# IR_ARRAY_IMG.net
KiCad netlist of a schematic drawn in EAGLE
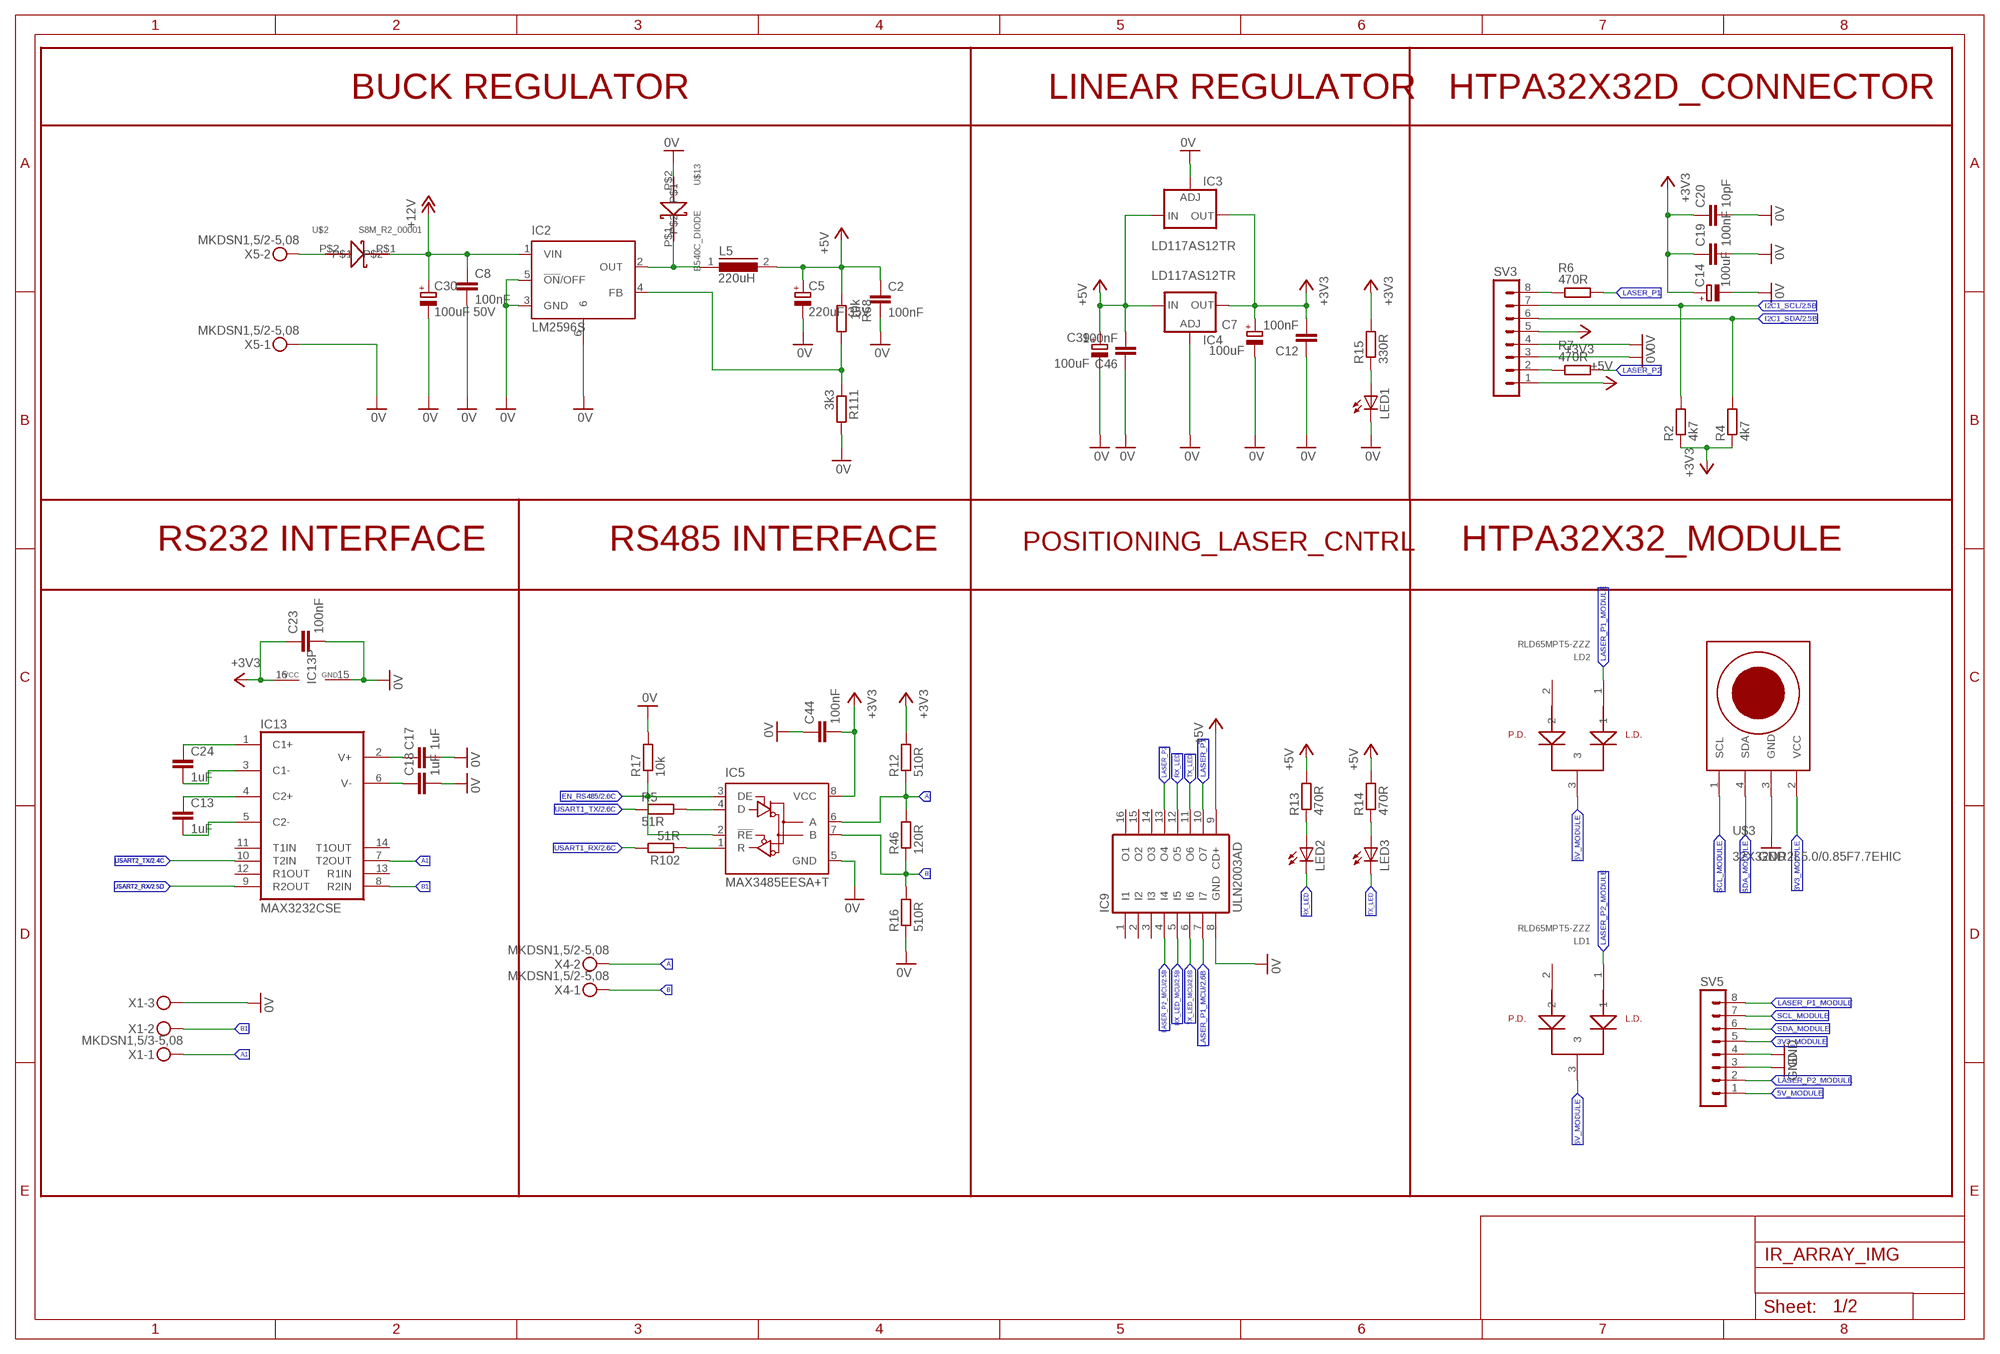
[diagram p0: schematic, sheet 1]
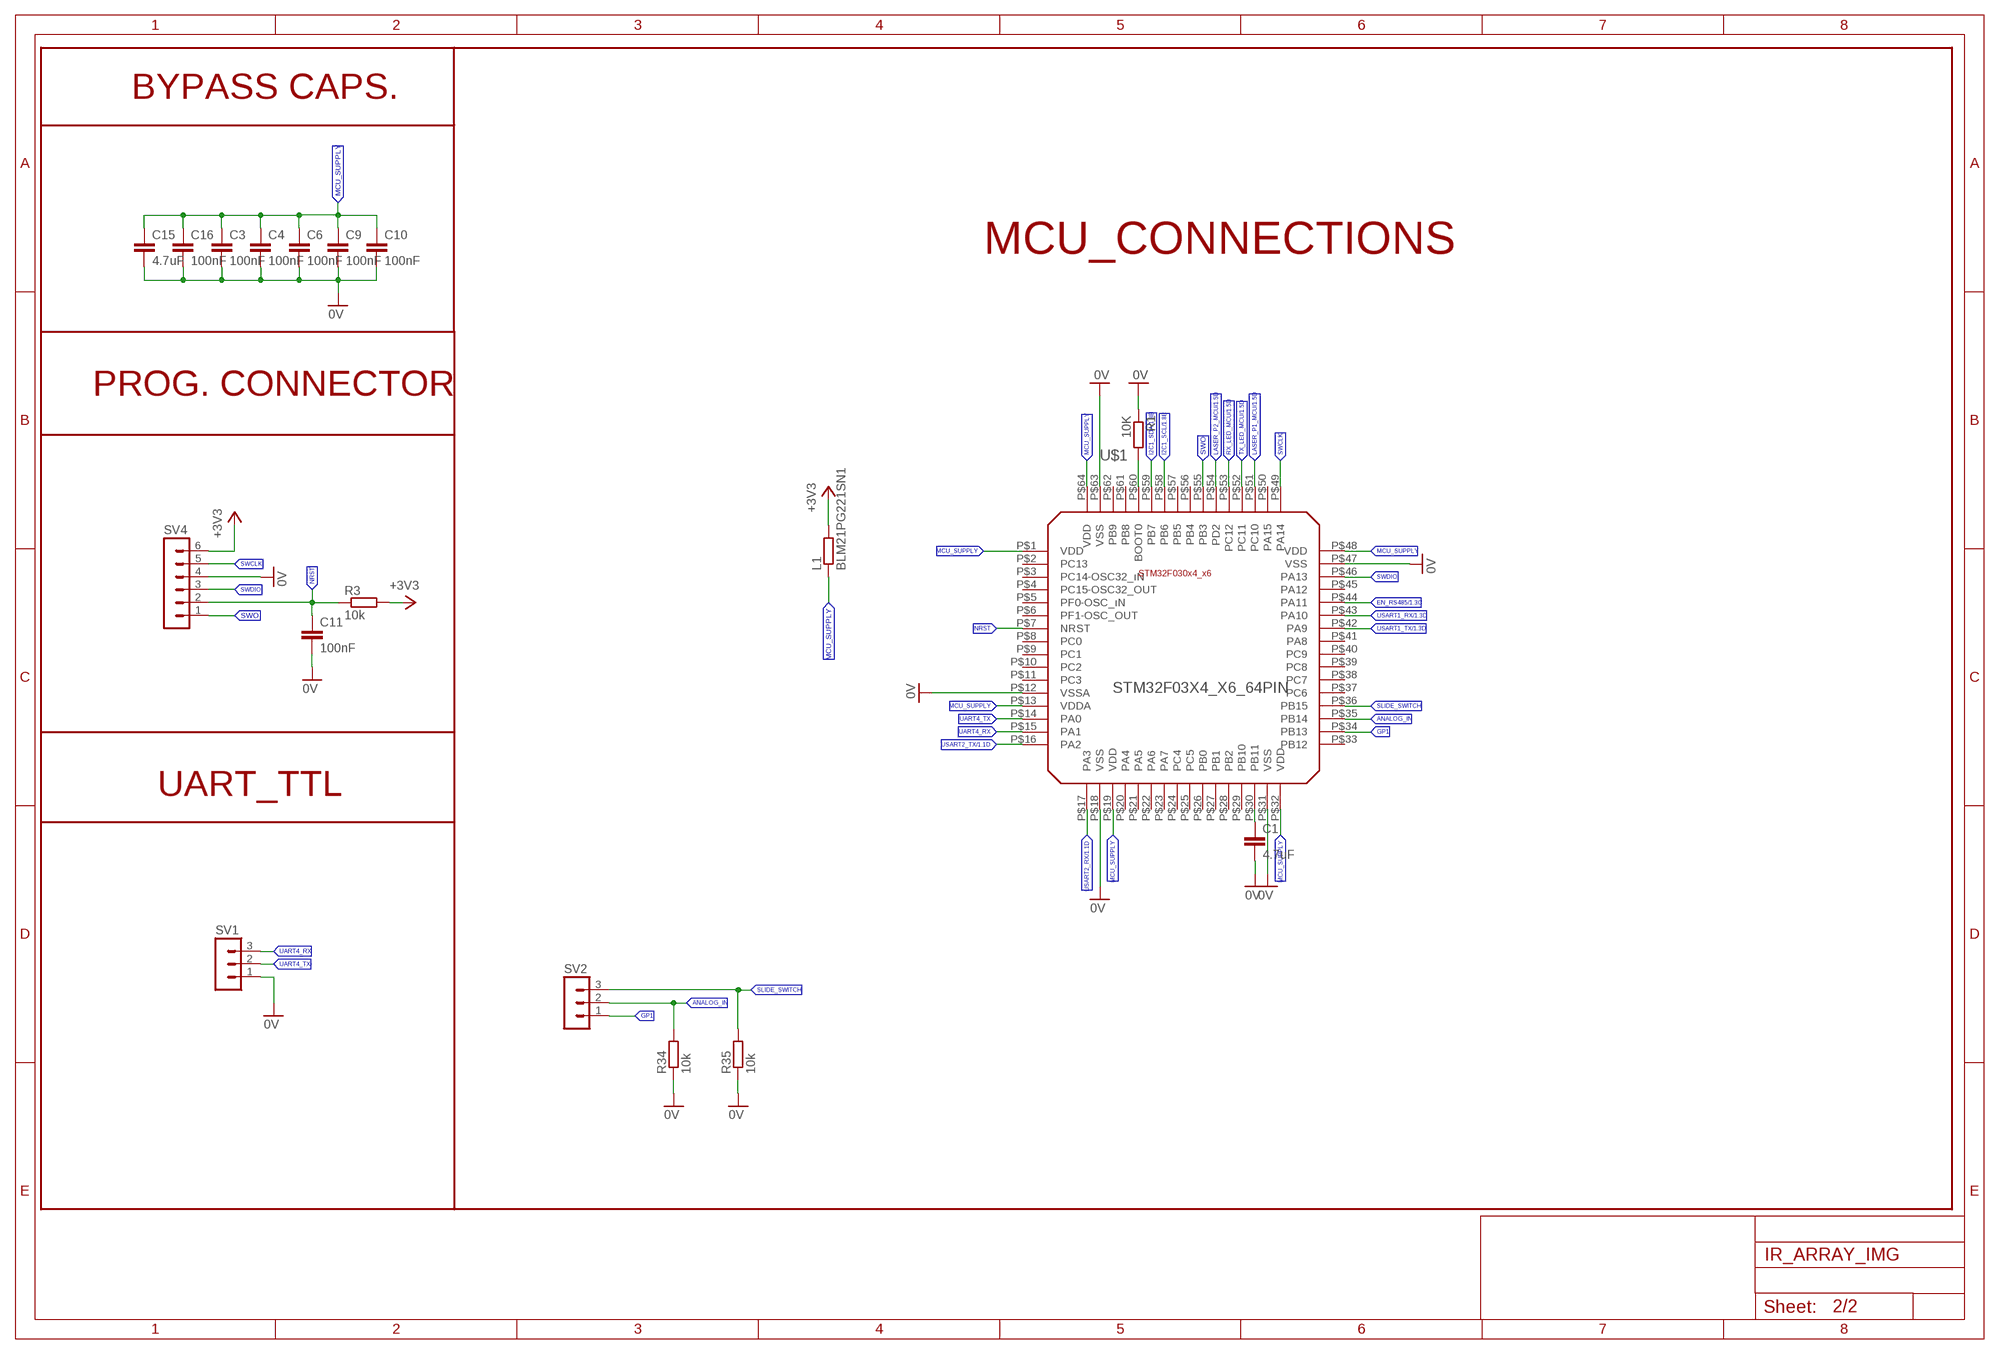
[diagram p1: schematic, sheet 2]

(export (version "E")
  (design (tool "Eeschema 10.0.6"))
  (components
    (comp (ref "C2")
      (value "100nF")
      (footprint "eagle-import:C0805")
      (libsource (lib "eagle-import") (part "C-EUC0805"))
    )
    (comp (ref "C5")
      (value "220uF 35V")
      (footprint "eagle-import:153CLV-0810")
      (libsource (lib "eagle-import") (part "CPOL-EU153CLV-0810"))
    )
    (comp (ref "C7")
      (value "100uF")
      (footprint "eagle-import:153CLV-0605")
      (libsource (lib "eagle-import") (part "CPOL-EU153CLV-0605"))
    )
    (comp (ref "C8")
      (value "100nF")
      (footprint "eagle-import:C0805")
      (libsource (lib "eagle-import") (part "C-EUC0805"))
    )
    (comp (ref "C12")
      (value "100nF")
      (footprint "eagle-import:C0603")
      (libsource (lib "eagle-import") (part "C-EUC0603"))
    )
    (comp (ref "C13")
      (value "1uF")
      (footprint "eagle-import:C1206")
      (libsource (lib "eagle-import") (part "C-EUC1206"))
    )
    (comp (ref "C14")
      (value "100uF")
      (footprint "eagle-import:C_6032-28R")
      (libsource (lib "eagle-import") (part "CPOL-EUC/6032-28R"))
    )
    (comp (ref "C17")
      (value "1uF")
      (footprint "eagle-import:C1206")
      (libsource (lib "eagle-import") (part "C-EUC1206"))
    )
    (comp (ref "C18")
      (value "1uF")
      (footprint "eagle-import:C1206")
      (libsource (lib "eagle-import") (part "C-EUC1206"))
    )
    (comp (ref "C19")
      (value "100nF")
      (footprint "eagle-import:C0603")
      (libsource (lib "eagle-import") (part "C-EUC0603"))
    )
    (comp (ref "C20")
      (value "10pF")
      (footprint "eagle-import:C0603")
      (libsource (lib "eagle-import") (part "C-EUC0603"))
    )
    (comp (ref "C23")
      (value "100nF")
      (footprint "eagle-import:C0603")
      (libsource (lib "eagle-import") (part "C-EUC0603"))
    )
    (comp (ref "C24")
      (value "1uF")
      (footprint "eagle-import:C1206")
      (libsource (lib "eagle-import") (part "C-EUC1206"))
    )
    (comp (ref "C30")
      (value "100uF 50V")
      (footprint "eagle-import:153CLV-0810")
      (libsource (lib "eagle-import") (part "CPOL-EU153CLV-0810"))
    )
    (comp (ref "C39")
      (value "100uF")
      (footprint "eagle-import:153CLV-0605")
      (libsource (lib "eagle-import") (part "CPOL-EU153CLV-0605"))
    )
    (comp (ref "C44")
      (value "100nF")
      (footprint "eagle-import:C0603")
      (libsource (lib "eagle-import") (part "C-EUC0603"))
    )
    (comp (ref "C46")
      (value "100nF")
      (footprint "eagle-import:C0603")
      (libsource (lib "eagle-import") (part "C-EUC0603"))
    )
    (comp (ref "IC2")
      (value "LM2596S")
      (footprint "eagle-import:TO263-5")
      (fields (field (name "MF") "NATIONAL SEMICONDUCTOR") (field (name "MPN") "LM2596S-ADJ/NOPB"))
      (libsource (lib "eagle-import") (part "LM2596S"))
    )
    (comp (ref "IC3")
      (value "LD117AS12TR")
      (footprint "eagle-import:SOT223")
      (libsource (lib "eagle-import") (part "LD117A?S12TR"))
    )
    (comp (ref "IC4")
      (value "LD117AS12TR")
      (footprint "eagle-import:SOT223")
      (libsource (lib "eagle-import") (part "LD117A?S12TR"))
    )
    (comp (ref "IC5")
      (value "MAX3485EESA+T")
      (footprint "eagle-import:D_R-PDSO-G8")
      (libsource (lib "eagle-import") (part "75176AD"))
    )
    (comp (ref "IC9")
      (value "ULN2003AD")
      (footprint "eagle-import:SO16")
      (libsource (lib "eagle-import") (part "ULN2003AD"))
    )
    (comp (ref "IC13")
      (value "MAX3232CSE")
      (footprint "eagle-import:SO16")
      (libsource (lib "eagle-import") (part "MAX3232SEC"))
    )
    (comp (ref "L5")
      (value "220uH")
      (footprint "eagle-import:DR125")
      (libsource (lib "eagle-import") (part "DR125"))
    )
    (comp (ref "LD1")
      (value "RLD65MPT5-ZZZ")
      (footprint "eagle-import:RLD65MPT5-ZZZ")
      (libsource (lib "eagle-import") (part "RLD65MPT5-ZZZ"))
    )
    (comp (ref "LD2")
      (value "RLD65MPT5-ZZZ")
      (footprint "eagle-import:RLD65MPT5-ZZZ")
      (libsource (lib "eagle-import") (part "RLD65MPT5-ZZZ"))
    )
    (comp (ref "LED1")
      (value "LEDCHIPLED_0805")
      (footprint "eagle-import:CHIPLED_0805")
      (libsource (lib "eagle-import") (part "LEDCHIPLED_0805"))
    )
    (comp (ref "LED2")
      (value "LEDCHIPLED_0805")
      (footprint "eagle-import:CHIPLED_0805")
      (libsource (lib "eagle-import") (part "LEDCHIPLED_0805"))
    )
    (comp (ref "LED3")
      (value "LEDCHIPLED_0805")
      (footprint "eagle-import:CHIPLED_0805")
      (libsource (lib "eagle-import") (part "LEDCHIPLED_0805"))
    )
    (comp (ref "R2")
      (value "4k7")
      (footprint "eagle-import:R0603")
      (libsource (lib "eagle-import") (part "R-EU_R0603"))
    )
    (comp (ref "R4")
      (value "4k7")
      (footprint "eagle-import:R0603")
      (libsource (lib "eagle-import") (part "R-EU_R0603"))
    )
    (comp (ref "R5")
      (value "51R")
      (footprint "eagle-import:R0603")
      (libsource (lib "eagle-import") (part "R-EU_R0603"))
    )
    (comp (ref "R6")
      (value "470R")
      (footprint "eagle-import:M0805")
      (libsource (lib "eagle-import") (part "R-EU_M0805"))
    )
    (comp (ref "R7")
      (value "470R")
      (footprint "eagle-import:M0805")
      (libsource (lib "eagle-import") (part "R-EU_M0805"))
    )
    (comp (ref "R12")
      (value "510R")
      (footprint "eagle-import:R0603")
      (libsource (lib "eagle-import") (part "R-EU_R0603"))
    )
    (comp (ref "R13")
      (value "470R")
      (footprint "eagle-import:R0603")
      (libsource (lib "eagle-import") (part "R-EU_R0603"))
    )
    (comp (ref "R14")
      (value "470R")
      (footprint "eagle-import:R0603")
      (libsource (lib "eagle-import") (part "R-EU_R0603"))
    )
    (comp (ref "R15")
      (value "330R")
      (footprint "eagle-import:R0603")
      (libsource (lib "eagle-import") (part "R-EU_R0603"))
    )
    (comp (ref "R16")
      (value "510R")
      (footprint "eagle-import:R0603")
      (libsource (lib "eagle-import") (part "R-EU_R0603"))
    )
    (comp (ref "R17")
      (value "10k")
      (footprint "eagle-import:R0603")
      (libsource (lib "eagle-import") (part "R-EU_R0603"))
    )
    (comp (ref "R46")
      (value "120R")
      (footprint "eagle-import:R0603")
      (libsource (lib "eagle-import") (part "R-EU_R0603"))
    )
    (comp (ref "R68")
      (value "10k")
      (footprint "eagle-import:M0805")
      (libsource (lib "eagle-import") (part "R-EU_M0805"))
    )
    (comp (ref "R102")
      (value "51R")
      (footprint "eagle-import:R0603")
      (libsource (lib "eagle-import") (part "R-EU_R0603"))
    )
    (comp (ref "R111")
      (value "3k3")
      (footprint "eagle-import:M0805")
      (libsource (lib "eagle-import") (part "R-EU_M0805"))
    )
    (comp (ref "SV3")
      (value "MA08-1")
      (footprint "eagle-import:MA08-1")
      (libsource (lib "eagle-import") (part "MA08-1"))
    )
    (comp (ref "SV5")
      (value "MA08-1")
      (footprint "eagle-import:MA08-1")
      (libsource (lib "eagle-import") (part "MA08-1"))
    )
    (comp (ref "U$2")
      (value "S8M_R2_00001")
      (footprint "eagle-import:SMC")
      (libsource (lib "eagle-import") (part "B540C_DIODE"))
    )
    (comp (ref "U$3")
      (value "32X32DR2L5.0/0.85F7.7EHIC")
      (footprint "eagle-import:32X32DR2L5.0_0.85F7.7EHIC")
      (libsource (lib "eagle-import") (part "32X32DR2L5.0/0.85F7.7EHIC"))
    )
    (comp (ref "U$13")
      (value "B540C_DIODE")
      (footprint "eagle-import:SMC")
      (libsource (lib "eagle-import") (part "B540C_DIODE"))
    )
    (comp (ref "X1")
      (value "MKDSN1,5/3-5,08")
      (footprint "eagle-import:MKDSN1,5_3-5,08")
      (libsource (lib "eagle-import") (part "MKDSN1,5/3-5,08"))
    )
    (comp (ref "X4")
      (value "MKDSN1,5/2-5,08")
      (footprint "eagle-import:MKDSN1,5_2-5,08")
      (libsource (lib "eagle-import") (part "MKDSN1,5/2-5,08"))
    )
    (comp (ref "X5")
      (value "MKDSN1,5/2-5,08")
      (footprint "eagle-import:MKDSN1,5_2-5,08")
      (libsource (lib "eagle-import") (part "MKDSN1,5/2-5,08"))
    )
    (comp (ref "C1")
      (value "4.7uF")
      (footprint "eagle-import:C0805")
      (libsource (lib "eagle-import") (part "C-EUC0805"))
    )
    (comp (ref "C3")
      (value "100nF")
      (footprint "eagle-import:C0603")
      (libsource (lib "eagle-import") (part "C-EUC0603"))
    )
    (comp (ref "C4")
      (value "100nF")
      (footprint "eagle-import:C0603")
      (libsource (lib "eagle-import") (part "C-EUC0603"))
    )
    (comp (ref "C6")
      (value "100nF")
      (footprint "eagle-import:C0603")
      (libsource (lib "eagle-import") (part "C-EUC0603"))
    )
    (comp (ref "C9")
      (value "100nF")
      (footprint "eagle-import:C0603")
      (libsource (lib "eagle-import") (part "C-EUC0603"))
    )
    (comp (ref "C10")
      (value "100nF")
      (footprint "eagle-import:C0603")
      (libsource (lib "eagle-import") (part "C-EUC0603"))
    )
    (comp (ref "C11")
      (value "100nF")
      (footprint "eagle-import:C0603")
      (libsource (lib "eagle-import") (part "C-EUC0603"))
    )
    (comp (ref "C15")
      (value "4.7uF")
      (footprint "eagle-import:C0805")
      (libsource (lib "eagle-import") (part "C-EUC0805"))
    )
    (comp (ref "C16")
      (value "100nF")
      (footprint "eagle-import:C0603")
      (libsource (lib "eagle-import") (part "C-EUC0603"))
    )
    (comp (ref "L1")
      (value "BLM21PG221SN1")
      (footprint "eagle-import:R0805")
      (libsource (lib "eagle-import") (part "R-EU_R0805"))
    )
    (comp (ref "R1")
      (value "10K")
      (footprint "eagle-import:R0603")
      (libsource (lib "eagle-import") (part "R-EU_R0603"))
    )
    (comp (ref "R3")
      (value "10k")
      (footprint "eagle-import:R0603")
      (libsource (lib "eagle-import") (part "R-EU_R0603"))
    )
    (comp (ref "R34")
      (value "10k")
      (footprint "eagle-import:R0603")
      (libsource (lib "eagle-import") (part "R-EU_R0603"))
    )
    (comp (ref "R35")
      (value "10k")
      (footprint "eagle-import:R0603")
      (libsource (lib "eagle-import") (part "R-EU_R0603"))
    )
    (comp (ref "SV1")
      (value "MA03-1")
      (footprint "eagle-import:MA03-1")
      (libsource (lib "eagle-import") (part "MA03-1"))
    )
    (comp (ref "SV2")
      (value "MA03-1")
      (footprint "eagle-import:MA03-1")
      (libsource (lib "eagle-import") (part "MA03-1"))
    )
    (comp (ref "SV4")
      (value "MA06-1")
      (footprint "eagle-import:MA06-1")
      (libsource (lib "eagle-import") (part "MA06-1"))
    )
    (comp (ref "U$1")
      (value "STM32F03X4_X6_64PIN")
      (footprint "eagle-import:LQFP64")
      (libsource (lib "eagle-import") (part "STM32F03X4_X6_64PIN"))
    )
  )
  (nets
    (net (code "1") (name "+3V3") (class "Default")
      (node (ref "C12") (pin "2") (pinfunction "2_2") (pintype "passive"))
      (node (ref "C14") (pin "+") (pinfunction "+_+") (pintype "passive"))
      (node (ref "C19") (pin "1") (pinfunction "1_1") (pintype "passive"))
      (node (ref "C20") (pin "1") (pinfunction "1_1") (pintype "passive"))
      (node (ref "C23") (pin "1") (pinfunction "1_1") (pintype "passive"))
      (node (ref "C44") (pin "2") (pinfunction "2_2") (pintype "passive"))
      (node (ref "C7") (pin "+") (pinfunction "+_+") (pintype "passive"))
      (node (ref "IC13") (pin "16") (pinfunction "VCC_16") (pintype "power_in"))
      (node (ref "IC3") (pin "4") (pinfunction "OUT_4") (pintype "passive"))
      (node (ref "IC4") (pin "4") (pinfunction "OUT_4") (pintype "passive"))
      (node (ref "IC5") (pin "8") (pinfunction "VCC_8") (pintype "power_in"))
      (node (ref "L1") (pin "2") (pinfunction "2_2") (pintype "passive"))
      (node (ref "R12") (pin "2") (pinfunction "2_2") (pintype "passive"))
      (node (ref "R15") (pin "2") (pinfunction "2_2") (pintype "passive"))
      (node (ref "R2") (pin "1") (pinfunction "1_1") (pintype "passive"))
      (node (ref "R3") (pin "2") (pinfunction "2_2") (pintype "passive"))
      (node (ref "R4") (pin "1") (pinfunction "1_1") (pintype "passive"))
      (node (ref "SV3") (pin "5") (pinfunction "5_5") (pintype "passive"))
      (node (ref "SV4") (pin "6") (pinfunction "6_6") (pintype "passive"))
    )
    (net (code "2") (name "+5V") (class "Default")
      (node (ref "C2") (pin "1") (pinfunction "1_1") (pintype "passive"))
      (node (ref "C39") (pin "+") (pinfunction "+_+") (pintype "passive"))
      (node (ref "C46") (pin "2") (pinfunction "2_2") (pintype "passive"))
      (node (ref "C5") (pin "+") (pinfunction "+_+") (pintype "passive"))
      (node (ref "IC3") (pin "3") (pinfunction "IN_3") (pintype "input"))
      (node (ref "IC4") (pin "3") (pinfunction "IN_3") (pintype "input"))
      (node (ref "IC9") (pin "9") (pinfunction "CD+_9") (pintype "passive"))
      (node (ref "L5") (pin "2") (pinfunction "2_2") (pintype "passive"))
      (node (ref "R13") (pin "2") (pinfunction "2_2") (pintype "passive"))
      (node (ref "R14") (pin "2") (pinfunction "2_2") (pintype "passive"))
      (node (ref "R68") (pin "1") (pinfunction "1_1") (pintype "passive"))
      (node (ref "SV3") (pin "1") (pinfunction "1_1") (pintype "passive"))
    )
    (net (code "3") (name "+12V") (class "Default")
      (node (ref "C30") (pin "+") (pinfunction "+_+") (pintype "passive"))
      (node (ref "C8") (pin "1") (pinfunction "1_1") (pintype "passive"))
      (node (ref "IC2") (pin "1") (pinfunction "VIN_1") (pintype "input"))
      (node (ref "U$2") (pin "P$1") (pinfunction "P$1_P$1") (pintype "bidirectional"))
    )
    (net (code "4") (name "0V") (class "Default")
      (node (ref "C1") (pin "2") (pinfunction "2_2") (pintype "passive"))
      (node (ref "C10") (pin "2") (pinfunction "2_2") (pintype "passive"))
      (node (ref "C11") (pin "2") (pinfunction "2_2") (pintype "passive"))
      (node (ref "C12") (pin "1") (pinfunction "1_1") (pintype "passive"))
      (node (ref "C14") (pin "-") (pinfunction "-_-") (pintype "passive"))
      (node (ref "C15") (pin "2") (pinfunction "2_2") (pintype "passive"))
      (node (ref "C16") (pin "2") (pinfunction "2_2") (pintype "passive"))
      (node (ref "C17") (pin "2") (pinfunction "2_2") (pintype "passive"))
      (node (ref "C18") (pin "2") (pinfunction "2_2") (pintype "passive"))
      (node (ref "C19") (pin "2") (pinfunction "2_2") (pintype "passive"))
      (node (ref "C2") (pin "2") (pinfunction "2_2") (pintype "passive"))
      (node (ref "C20") (pin "2") (pinfunction "2_2") (pintype "passive"))
      (node (ref "C23") (pin "2") (pinfunction "2_2") (pintype "passive"))
      (node (ref "C3") (pin "2") (pinfunction "2_2") (pintype "passive"))
      (node (ref "C30") (pin "-") (pinfunction "-_-") (pintype "passive"))
      (node (ref "C39") (pin "-") (pinfunction "-_-") (pintype "passive"))
      (node (ref "C4") (pin "2") (pinfunction "2_2") (pintype "passive"))
      (node (ref "C44") (pin "1") (pinfunction "1_1") (pintype "passive"))
      (node (ref "C46") (pin "1") (pinfunction "1_1") (pintype "passive"))
      (node (ref "C5") (pin "-") (pinfunction "-_-") (pintype "passive"))
      (node (ref "C6") (pin "2") (pinfunction "2_2") (pintype "passive"))
      (node (ref "C7") (pin "-") (pinfunction "-_-") (pintype "passive"))
      (node (ref "C8") (pin "2") (pinfunction "2_2") (pintype "passive"))
      (node (ref "C9") (pin "2") (pinfunction "2_2") (pintype "passive"))
      (node (ref "IC13") (pin "15") (pinfunction "GND_15") (pintype "power_in"))
      (node (ref "IC2") (pin "3") (pinfunction "GND_3") (pintype "power_in"))
      (node (ref "IC2") (pin "5") (pinfunction "~{ON}/OFF_5") (pintype "input"))
      (node (ref "IC2") (pin "6") (pinfunction "6_6") (pintype "bidirectional"))
      (node (ref "IC3") (pin "1") (pinfunction "ADJ_1") (pintype "input"))
      (node (ref "IC4") (pin "1") (pinfunction "ADJ_1") (pintype "input"))
      (node (ref "IC5") (pin "5") (pinfunction "GND_5") (pintype "power_in"))
      (node (ref "IC9") (pin "8") (pinfunction "GND_8") (pintype "power_in"))
      (node (ref "LED1") (pin "C") (pinfunction "C_C") (pintype "passive"))
      (node (ref "R1") (pin "1") (pinfunction "1_1") (pintype "passive"))
      (node (ref "R111") (pin "2") (pinfunction "2_2") (pintype "passive"))
      (node (ref "R16") (pin "1") (pinfunction "1_1") (pintype "passive"))
      (node (ref "R17") (pin "2") (pinfunction "2_2") (pintype "passive"))
      (node (ref "R34") (pin "1") (pinfunction "1_1") (pintype "passive"))
      (node (ref "R35") (pin "1") (pinfunction "1_1") (pintype "passive"))
      (node (ref "SV1") (pin "1") (pinfunction "1_1") (pintype "passive"))
      (node (ref "SV3") (pin "3") (pinfunction "3_3") (pintype "passive"))
      (node (ref "SV3") (pin "4") (pinfunction "4_4") (pintype "passive"))
      (node (ref "SV4") (pin "4") (pinfunction "4_4") (pintype "passive"))
      (node (ref "U$1") (pin "P$12") (pinfunction "VSSA_P$12") (pintype "bidirectional"))
      (node (ref "U$1") (pin "P$18") (pinfunction "VSS_P$18") (pintype "bidirectional"))
      (node (ref "U$1") (pin "P$31") (pinfunction "VSS_P$31") (pintype "bidirectional"))
      (node (ref "U$1") (pin "P$47") (pinfunction "VSS_P$47") (pintype "bidirectional"))
      (node (ref "U$1") (pin "P$63") (pinfunction "VSS_P$63") (pintype "bidirectional"))
      (node (ref "U$13") (pin "P$2") (pinfunction "P$2_P$2") (pintype "bidirectional"))
      (node (ref "X1") (pin "3") (pinfunction "KL_3") (pintype "passive"))
      (node (ref "X5") (pin "1") (pinfunction "KL_1") (pintype "passive"))
    )
    (net (code "5") (name "3V3_MODULE") (class "Default")
      (node (ref "SV5") (pin "5") (pinfunction "5_5") (pintype "passive"))
      (node (ref "U$3") (pin "2") (pinfunction "VCC_2") (pintype "bidirectional"))
    )
    (net (code "6") (name "5V_MODULE") (class "Default")
      (node (ref "LD1") (pin "3") (pinfunction "3_3") (pintype "bidirectional"))
      (node (ref "LD2") (pin "3") (pinfunction "3_3") (pintype "bidirectional"))
      (node (ref "SV5") (pin "1") (pinfunction "1_1") (pintype "passive"))
    )
    (net (code "7") (name "A") (class "Default")
      (node (ref "IC5") (pin "6") (pinfunction "A_6") (pintype "output"))
      (node (ref "R12") (pin "1") (pinfunction "1_1") (pintype "passive"))
      (node (ref "R46") (pin "2") (pinfunction "2_2") (pintype "passive"))
      (node (ref "X4") (pin "2") (pinfunction "KL_2") (pintype "passive"))
    )
    (net (code "8") (name "A1") (class "Default")
      (node (ref "IC13") (pin "7") (pinfunction "T2OUT_7") (pintype "output"))
      (node (ref "X1") (pin "1") (pinfunction "KL_1") (pintype "passive"))
    )
    (net (code "9") (name "ANALOG_IN") (class "Default")
      (node (ref "R34") (pin "2") (pinfunction "2_2") (pintype "passive"))
      (node (ref "SV2") (pin "2") (pinfunction "2_2") (pintype "passive"))
      (node (ref "U$1") (pin "P$35") (pinfunction "PB14_P$35") (pintype "bidirectional"))
    )
    (net (code "10") (name "B") (class "Default")
      (node (ref "IC5") (pin "7") (pinfunction "B_7") (pintype "output"))
      (node (ref "R16") (pin "2") (pinfunction "2_2") (pintype "passive"))
      (node (ref "R46") (pin "1") (pinfunction "1_1") (pintype "passive"))
      (node (ref "X4") (pin "1") (pinfunction "KL_1") (pintype "passive"))
    )
    (net (code "11") (name "B1") (class "Default")
      (node (ref "IC13") (pin "8") (pinfunction "R2IN_8") (pintype "input"))
      (node (ref "X1") (pin "2") (pinfunction "KL_2") (pintype "passive"))
    )
    (net (code "12") (name "EN_RS485") (class "Default")
      (node (ref "IC5") (pin "2") (pinfunction "~{RE}_2") (pintype "input"))
      (node (ref "IC5") (pin "3") (pinfunction "DE_3") (pintype "input"))
      (node (ref "R17") (pin "1") (pinfunction "1_1") (pintype "passive"))
      (node (ref "U$1") (pin "P$44") (pinfunction "PA11_P$44") (pintype "bidirectional"))
    )
    (net (code "13") (name "GND") (class "Default")
      (node (ref "SV5") (pin "3") (pinfunction "3_3") (pintype "passive"))
      (node (ref "SV5") (pin "4") (pinfunction "4_4") (pintype "passive"))
      (node (ref "U$3") (pin "3") (pinfunction "GND_3") (pintype "bidirectional"))
    )
    (net (code "14") (name "GP1") (class "Default")
      (node (ref "SV2") (pin "1") (pinfunction "1_1") (pintype "passive"))
      (node (ref "U$1") (pin "P$34") (pinfunction "PB13_P$34") (pintype "bidirectional"))
    )
    (net (code "15") (name "I2C1_SCL") (class "Default")
      (node (ref "R2") (pin "2") (pinfunction "2_2") (pintype "passive"))
      (node (ref "SV3") (pin "7") (pinfunction "7_7") (pintype "passive"))
      (node (ref "U$1") (pin "P$58") (pinfunction "PB6_P$58") (pintype "bidirectional"))
    )
    (net (code "16") (name "I2C1_SDA") (class "Default")
      (node (ref "R4") (pin "2") (pinfunction "2_2") (pintype "passive"))
      (node (ref "SV3") (pin "6") (pinfunction "6_6") (pintype "passive"))
      (node (ref "U$1") (pin "P$59") (pinfunction "PB7_P$59") (pintype "bidirectional"))
    )
    (net (code "17") (name "LASER_P1") (class "Default")
      (node (ref "IC9") (pin "10") (pinfunction "O7_10") (pintype "open_collector"))
      (node (ref "R6") (pin "2") (pinfunction "2_2") (pintype "passive"))
    )
    (net (code "18") (name "LASER_P1_MCU") (class "Default")
      (node (ref "IC9") (pin "7") (pinfunction "I7_7") (pintype "input"))
      (node (ref "U$1") (pin "P$51") (pinfunction "PC10_P$51") (pintype "bidirectional"))
    )
    (net (code "19") (name "LASER_P1_MODULE") (class "Default")
      (node (ref "LD2") (pin "1") (pinfunction "1_1") (pintype "bidirectional"))
      (node (ref "SV5") (pin "8") (pinfunction "8_8") (pintype "passive"))
    )
    (net (code "20") (name "LASER_P2") (class "Default")
      (node (ref "IC9") (pin "13") (pinfunction "O4_13") (pintype "open_collector"))
      (node (ref "R7") (pin "2") (pinfunction "2_2") (pintype "passive"))
    )
    (net (code "21") (name "LASER_P2_MCU") (class "Default")
      (node (ref "IC9") (pin "4") (pinfunction "I4_4") (pintype "input"))
      (node (ref "U$1") (pin "P$54") (pinfunction "PD2_P$54") (pintype "bidirectional"))
    )
    (net (code "22") (name "LASER_P2_MODULE") (class "Default")
      (node (ref "LD1") (pin "1") (pinfunction "1_1") (pintype "bidirectional"))
      (node (ref "SV5") (pin "2") (pinfunction "2_2") (pintype "passive"))
    )
    (net (code "23") (name "MCU_SUPPLY") (class "Default")
      (node (ref "C10") (pin "1") (pinfunction "1_1") (pintype "passive"))
      (node (ref "C15") (pin "1") (pinfunction "1_1") (pintype "passive"))
      (node (ref "C16") (pin "1") (pinfunction "1_1") (pintype "passive"))
      (node (ref "C3") (pin "1") (pinfunction "1_1") (pintype "passive"))
      (node (ref "C4") (pin "1") (pinfunction "1_1") (pintype "passive"))
      (node (ref "C6") (pin "1") (pinfunction "1_1") (pintype "passive"))
      (node (ref "C9") (pin "1") (pinfunction "1_1") (pintype "passive"))
      (node (ref "L1") (pin "1") (pinfunction "1_1") (pintype "passive"))
      (node (ref "U$1") (pin "P$1") (pinfunction "VDD_P$1") (pintype "bidirectional"))
      (node (ref "U$1") (pin "P$13") (pinfunction "VDDA_P$13") (pintype "bidirectional"))
      (node (ref "U$1") (pin "P$19") (pinfunction "VDD_P$19") (pintype "bidirectional"))
      (node (ref "U$1") (pin "P$32") (pinfunction "VDD_P$32") (pintype "bidirectional"))
      (node (ref "U$1") (pin "P$48") (pinfunction "VDD_P$48") (pintype "bidirectional"))
      (node (ref "U$1") (pin "P$64") (pinfunction "VDD_P$64") (pintype "bidirectional"))
    )
    (net (code "24") (name "NRST") (class "Default")
      (node (ref "C11") (pin "1") (pinfunction "1_1") (pintype "passive"))
      (node (ref "R3") (pin "1") (pinfunction "1_1") (pintype "passive"))
      (node (ref "SV4") (pin "2") (pinfunction "2_2") (pintype "passive"))
      (node (ref "U$1") (pin "P$7") (pinfunction "NRST_P$7") (pintype "bidirectional"))
    )
    (net (code "25") (name "Net-(IC2-FB)") (class "Default")
      (node (ref "IC2") (pin "4") (pinfunction "FB_4") (pintype "input"))
      (node (ref "R111") (pin "1") (pinfunction "1_1") (pintype "passive"))
      (node (ref "R68") (pin "2") (pinfunction "2_2") (pintype "passive"))
    )
    (net (code "26") (name "Net-(IC2-OUT)") (class "Default")
      (node (ref "IC2") (pin "2") (pinfunction "OUT_2") (pintype "output"))
      (node (ref "L5") (pin "1") (pinfunction "1_1") (pintype "passive"))
      (node (ref "U$13") (pin "P$1") (pinfunction "P$1_P$1") (pintype "bidirectional"))
    )
    (net (code "27") (name "Net-(IC5-D)") (class "Default")
      (node (ref "IC5") (pin "4") (pinfunction "D_4") (pintype "input"))
      (node (ref "R5") (pin "2") (pinfunction "2_2") (pintype "passive"))
    )
    (net (code "28") (name "Net-(IC5-R)") (class "Default")
      (node (ref "IC5") (pin "1") (pinfunction "R_1") (pintype "input"))
      (node (ref "R102") (pin "1") (pinfunction "1_1") (pintype "passive"))
    )
    (net (code "29") (name "Net-(IC13A-C1+)") (class "Default")
      (node (ref "C24") (pin "1") (pinfunction "1_1") (pintype "passive"))
      (node (ref "IC13") (pin "1") (pinfunction "C1+_1") (pintype "bidirectional"))
    )
    (net (code "30") (name "Net-(IC13A-C1-)") (class "Default")
      (node (ref "C24") (pin "2") (pinfunction "2_2") (pintype "passive"))
      (node (ref "IC13") (pin "3") (pinfunction "C1-_3") (pintype "bidirectional"))
    )
    (net (code "31") (name "Net-(IC13A-C2+)") (class "Default")
      (node (ref "C13") (pin "1") (pinfunction "1_1") (pintype "passive"))
      (node (ref "IC13") (pin "4") (pinfunction "C2+_4") (pintype "bidirectional"))
    )
    (net (code "32") (name "Net-(IC13A-C2-)") (class "Default")
      (node (ref "C13") (pin "2") (pinfunction "2_2") (pintype "passive"))
      (node (ref "IC13") (pin "5") (pinfunction "C2-_5") (pintype "bidirectional"))
    )
    (net (code "33") (name "Net-(IC13A-V+)") (class "Default")
      (node (ref "C17") (pin "1") (pinfunction "1_1") (pintype "passive"))
      (node (ref "IC13") (pin "2") (pinfunction "V+_2") (pintype "bidirectional"))
    )
    (net (code "34") (name "Net-(IC13A-V-)") (class "Default")
      (node (ref "C18") (pin "1") (pinfunction "1_1") (pintype "passive"))
      (node (ref "IC13") (pin "6") (pinfunction "V-_6") (pintype "bidirectional"))
    )
    (net (code "35") (name "Net-(LED1-PadA)") (class "Default")
      (node (ref "LED1") (pin "A") (pinfunction "A_A") (pintype "passive"))
      (node (ref "R15") (pin "1") (pinfunction "1_1") (pintype "passive"))
    )
    (net (code "36") (name "Net-(LED2-PadA)") (class "Default")
      (node (ref "LED2") (pin "A") (pinfunction "A_A") (pintype "passive"))
      (node (ref "R13") (pin "1") (pinfunction "1_1") (pintype "passive"))
    )
    (net (code "37") (name "Net-(LED3-PadA)") (class "Default")
      (node (ref "LED3") (pin "A") (pinfunction "A_A") (pintype "passive"))
      (node (ref "R14") (pin "1") (pinfunction "1_1") (pintype "passive"))
    )
    (net (code "38") (name "Net-(R6-Pad1)") (class "Default")
      (node (ref "R6") (pin "1") (pinfunction "1_1") (pintype "passive"))
      (node (ref "SV3") (pin "8") (pinfunction "8_8") (pintype "passive"))
    )
    (net (code "39") (name "Net-(R7-Pad1)") (class "Default")
      (node (ref "R7") (pin "1") (pinfunction "1_1") (pintype "passive"))
      (node (ref "SV3") (pin "2") (pinfunction "2_2") (pintype "passive"))
    )
    (net (code "40") (name "Net-(U$1-BOOT0)") (class "Default")
      (node (ref "R1") (pin "2") (pinfunction "2_2") (pintype "passive"))
      (node (ref "U$1") (pin "P$60") (pinfunction "BOOT0_P$60") (pintype "bidirectional"))
    )
    (net (code "41") (name "Net-(U$1-PB11)") (class "Default")
      (node (ref "C1") (pin "1") (pinfunction "1_1") (pintype "passive"))
      (node (ref "U$1") (pin "P$30") (pinfunction "PB11_P$30") (pintype "bidirectional"))
    )
    (net (code "42") (name "Net-(X5B-KL)") (class "Default")
      (node (ref "U$2") (pin "P$2") (pinfunction "P$2_P$2") (pintype "bidirectional"))
      (node (ref "X5") (pin "2") (pinfunction "KL_2") (pintype "passive"))
    )
    (net (code "43") (name "RX_LED") (class "Default")
      (node (ref "IC9") (pin "12") (pinfunction "O5_12") (pintype "open_collector"))
      (node (ref "LED2") (pin "C") (pinfunction "C_C") (pintype "passive"))
    )
    (net (code "44") (name "RX_LED_MCU") (class "Default")
      (node (ref "IC9") (pin "5") (pinfunction "I5_5") (pintype "input"))
      (node (ref "U$1") (pin "P$53") (pinfunction "PC12_P$53") (pintype "bidirectional"))
    )
    (net (code "45") (name "SCL_MODULE") (class "Default")
      (node (ref "SV5") (pin "7") (pinfunction "7_7") (pintype "passive"))
      (node (ref "U$3") (pin "1") (pinfunction "SCL_1") (pintype "bidirectional"))
    )
    (net (code "46") (name "SDA_MODULE") (class "Default")
      (node (ref "SV5") (pin "6") (pinfunction "6_6") (pintype "passive"))
      (node (ref "U$3") (pin "4") (pinfunction "SDA_4") (pintype "bidirectional"))
    )
    (net (code "47") (name "SLIDE_SWITCH") (class "Default")
      (node (ref "R35") (pin "2") (pinfunction "2_2") (pintype "passive"))
      (node (ref "SV2") (pin "3") (pinfunction "3_3") (pintype "passive"))
      (node (ref "U$1") (pin "P$36") (pinfunction "PB15_P$36") (pintype "bidirectional"))
    )
    (net (code "48") (name "SWCLK") (class "Default")
      (node (ref "SV4") (pin "5") (pinfunction "5_5") (pintype "passive"))
      (node (ref "U$1") (pin "P$49") (pinfunction "PA14_P$49") (pintype "bidirectional"))
    )
    (net (code "49") (name "SWDIO") (class "Default")
      (node (ref "SV4") (pin "3") (pinfunction "3_3") (pintype "passive"))
      (node (ref "U$1") (pin "P$46") (pinfunction "PA13_P$46") (pintype "bidirectional"))
    )
    (net (code "50") (name "SWO") (class "Default")
      (node (ref "SV4") (pin "1") (pinfunction "1_1") (pintype "passive"))
      (node (ref "U$1") (pin "P$55") (pinfunction "PB3_P$55") (pintype "bidirectional"))
    )
    (net (code "51") (name "TX_LED") (class "Default")
      (node (ref "IC9") (pin "11") (pinfunction "O6_11") (pintype "open_collector"))
      (node (ref "LED3") (pin "C") (pinfunction "C_C") (pintype "passive"))
    )
    (net (code "52") (name "TX_LED_MCU") (class "Default")
      (node (ref "IC9") (pin "6") (pinfunction "I6_6") (pintype "input"))
      (node (ref "U$1") (pin "P$52") (pinfunction "PC11_P$52") (pintype "bidirectional"))
    )
    (net (code "53") (name "UART4_RX") (class "Default")
      (node (ref "SV1") (pin "3") (pinfunction "3_3") (pintype "passive"))
      (node (ref "U$1") (pin "P$15") (pinfunction "PA1_P$15") (pintype "bidirectional"))
    )
    (net (code "54") (name "UART4_TX") (class "Default")
      (node (ref "SV1") (pin "2") (pinfunction "2_2") (pintype "passive"))
      (node (ref "U$1") (pin "P$14") (pinfunction "PA0_P$14") (pintype "bidirectional"))
    )
    (net (code "55") (name "USART1_RX") (class "Default")
      (node (ref "R102") (pin "2") (pinfunction "2_2") (pintype "passive"))
      (node (ref "U$1") (pin "P$43") (pinfunction "PA10_P$43") (pintype "bidirectional"))
    )
    (net (code "56") (name "USART1_TX") (class "Default")
      (node (ref "R5") (pin "1") (pinfunction "1_1") (pintype "passive"))
      (node (ref "U$1") (pin "P$42") (pinfunction "PA9_P$42") (pintype "bidirectional"))
    )
    (net (code "57") (name "USART2_RX") (class "Default")
      (node (ref "IC13") (pin "9") (pinfunction "R2OUT_9") (pintype "output"))
      (node (ref "U$1") (pin "P$17") (pinfunction "PA3_P$17") (pintype "bidirectional"))
    )
    (net (code "58") (name "USART2_TX") (class "Default")
      (node (ref "IC13") (pin "10") (pinfunction "T2IN_10") (pintype "input"))
      (node (ref "U$1") (pin "P$16") (pinfunction "PA2_P$16") (pintype "bidirectional"))
    )
    (net (code "59") (name "unconnected-(IC9-I1-Pad1)") (class "Default")
      (node (ref "IC9") (pin "1") (pinfunction "I1_1") (pintype "input"))
    )
    (net (code "60") (name "unconnected-(IC9-I2-Pad2)") (class "Default")
      (node (ref "IC9") (pin "2") (pinfunction "I2_2") (pintype "input"))
    )
    (net (code "61") (name "unconnected-(IC9-I3-Pad3)") (class "Default")
      (node (ref "IC9") (pin "3") (pinfunction "I3_3") (pintype "input"))
    )
    (net (code "62") (name "unconnected-(IC9-O1-Pad16)") (class "Default")
      (node (ref "IC9") (pin "16") (pinfunction "O1_16") (pintype "open_collector"))
    )
    (net (code "63") (name "unconnected-(IC9-O2-Pad15)") (class "Default")
      (node (ref "IC9") (pin "15") (pinfunction "O2_15") (pintype "open_collector"))
    )
    (net (code "64") (name "unconnected-(IC9-O3-Pad14)") (class "Default")
      (node (ref "IC9") (pin "14") (pinfunction "O3_14") (pintype "open_collector"))
    )
    (net (code "65") (name "unconnected-(IC13A-R1IN-Pad13)") (class "Default")
      (node (ref "IC13") (pin "13") (pinfunction "R1IN_13") (pintype "input"))
    )
    (net (code "66") (name "unconnected-(IC13A-R1OUT-Pad12)") (class "Default")
      (node (ref "IC13") (pin "12") (pinfunction "R1OUT_12") (pintype "output"))
    )
    (net (code "67") (name "unconnected-(IC13A-T1IN-Pad11)") (class "Default")
      (node (ref "IC13") (pin "11") (pinfunction "T1IN_11") (pintype "input"))
    )
    (net (code "68") (name "unconnected-(IC13A-T1OUT-Pad14)") (class "Default")
      (node (ref "IC13") (pin "14") (pinfunction "T1OUT_14") (pintype "output"))
    )
    (net (code "69") (name "unconnected-(LD1-Pad2)") (class "Default")
      (node (ref "LD1") (pin "2") (pinfunction "2_2") (pintype "bidirectional"))
    )
    (net (code "70") (name "unconnected-(LD2-Pad2)") (class "Default")
      (node (ref "LD2") (pin "2") (pinfunction "2_2") (pintype "bidirectional"))
    )
    (net (code "71") (name "unconnected-(U$1-PA4-PadP$20)") (class "Default")
      (node (ref "U$1") (pin "P$20") (pinfunction "PA4_P$20") (pintype "bidirectional"))
    )
    (net (code "72") (name "unconnected-(U$1-PA5-PadP$21)") (class "Default")
      (node (ref "U$1") (pin "P$21") (pinfunction "PA5_P$21") (pintype "bidirectional"))
    )
    (net (code "73") (name "unconnected-(U$1-PA6-PadP$22)") (class "Default")
      (node (ref "U$1") (pin "P$22") (pinfunction "PA6_P$22") (pintype "bidirectional"))
    )
    (net (code "74") (name "unconnected-(U$1-PA7-PadP$23)") (class "Default")
      (node (ref "U$1") (pin "P$23") (pinfunction "PA7_P$23") (pintype "bidirectional"))
    )
    (net (code "75") (name "unconnected-(U$1-PA8-PadP$41)") (class "Default")
      (node (ref "U$1") (pin "P$41") (pinfunction "PA8_P$41") (pintype "bidirectional"))
    )
    (net (code "76") (name "unconnected-(U$1-PA12-PadP$45)") (class "Default")
      (node (ref "U$1") (pin "P$45") (pinfunction "PA12_P$45") (pintype "bidirectional"))
    )
    (net (code "77") (name "unconnected-(U$1-PA15-PadP$50)") (class "Default")
      (node (ref "U$1") (pin "P$50") (pinfunction "PA15_P$50") (pintype "bidirectional"))
    )
    (net (code "78") (name "unconnected-(U$1-PB0-PadP$26)") (class "Default")
      (node (ref "U$1") (pin "P$26") (pinfunction "PB0_P$26") (pintype "bidirectional"))
    )
    (net (code "79") (name "unconnected-(U$1-PB1-PadP$27)") (class "Default")
      (node (ref "U$1") (pin "P$27") (pinfunction "PB1_P$27") (pintype "bidirectional"))
    )
    (net (code "80") (name "unconnected-(U$1-PB2-PadP$28)") (class "Default")
      (node (ref "U$1") (pin "P$28") (pinfunction "PB2_P$28") (pintype "bidirectional"))
    )
    (net (code "81") (name "unconnected-(U$1-PB4-PadP$56)") (class "Default")
      (node (ref "U$1") (pin "P$56") (pinfunction "PB4_P$56") (pintype "bidirectional"))
    )
    (net (code "82") (name "unconnected-(U$1-PB5-PadP$57)") (class "Default")
      (node (ref "U$1") (pin "P$57") (pinfunction "PB5_P$57") (pintype "bidirectional"))
    )
    (net (code "83") (name "unconnected-(U$1-PB8-PadP$61)") (class "Default")
      (node (ref "U$1") (pin "P$61") (pinfunction "PB8_P$61") (pintype "bidirectional"))
    )
    (net (code "84") (name "unconnected-(U$1-PB9-PadP$62)") (class "Default")
      (node (ref "U$1") (pin "P$62") (pinfunction "PB9_P$62") (pintype "bidirectional"))
    )
    (net (code "85") (name "unconnected-(U$1-PB10-PadP$29)") (class "Default")
      (node (ref "U$1") (pin "P$29") (pinfunction "PB10_P$29") (pintype "bidirectional"))
    )
    (net (code "86") (name "unconnected-(U$1-PB12-PadP$33)") (class "Default")
      (node (ref "U$1") (pin "P$33") (pinfunction "PB12_P$33") (pintype "bidirectional"))
    )
    (net (code "87") (name "unconnected-(U$1-PC0-PadP$8)") (class "Default")
      (node (ref "U$1") (pin "P$8") (pinfunction "PC0_P$8") (pintype "bidirectional"))
    )
    (net (code "88") (name "unconnected-(U$1-PC1-PadP$9)") (class "Default")
      (node (ref "U$1") (pin "P$9") (pinfunction "PC1_P$9") (pintype "bidirectional"))
    )
    (net (code "89") (name "unconnected-(U$1-PC2-PadP$10)") (class "Default")
      (node (ref "U$1") (pin "P$10") (pinfunction "PC2_P$10") (pintype "bidirectional"))
    )
    (net (code "90") (name "unconnected-(U$1-PC3-PadP$11)") (class "Default")
      (node (ref "U$1") (pin "P$11") (pinfunction "PC3_P$11") (pintype "bidirectional"))
    )
    (net (code "91") (name "unconnected-(U$1-PC4-PadP$24)") (class "Default")
      (node (ref "U$1") (pin "P$24") (pinfunction "PC4_P$24") (pintype "bidirectional"))
    )
    (net (code "92") (name "unconnected-(U$1-PC5-PadP$25)") (class "Default")
      (node (ref "U$1") (pin "P$25") (pinfunction "PC5_P$25") (pintype "bidirectional"))
    )
    (net (code "93") (name "unconnected-(U$1-PC6-PadP$37)") (class "Default")
      (node (ref "U$1") (pin "P$37") (pinfunction "PC6_P$37") (pintype "bidirectional"))
    )
    (net (code "94") (name "unconnected-(U$1-PC7-PadP$38)") (class "Default")
      (node (ref "U$1") (pin "P$38") (pinfunction "PC7_P$38") (pintype "bidirectional"))
    )
    (net (code "95") (name "unconnected-(U$1-PC8-PadP$39)") (class "Default")
      (node (ref "U$1") (pin "P$39") (pinfunction "PC8_P$39") (pintype "bidirectional"))
    )
    (net (code "96") (name "unconnected-(U$1-PC9-PadP$40)") (class "Default")
      (node (ref "U$1") (pin "P$40") (pinfunction "PC9_P$40") (pintype "bidirectional"))
    )
    (net (code "97") (name "unconnected-(U$1-PC13-PadP$2)") (class "Default")
      (node (ref "U$1") (pin "P$2") (pinfunction "PC13_P$2") (pintype "bidirectional"))
    )
    (net (code "98") (name "unconnected-(U$1-PC14-OSC32_ıN-PadP$3)") (class "Default")
      (node (ref "U$1") (pin "P$3") (pinfunction "PC14-OSC32_ıN_P$3") (pintype "bidirectional"))
    )
    (net (code "99") (name "unconnected-(U$1-PC15-OSC32_OUT-PadP$4)") (class "Default")
      (node (ref "U$1") (pin "P$4") (pinfunction "PC15-OSC32_OUT_P$4") (pintype "bidirectional"))
    )
    (net (code "100") (name "unconnected-(U$1-PF0-OSC_ıN-PadP$5)") (class "Default")
      (node (ref "U$1") (pin "P$5") (pinfunction "PF0-OSC_ıN_P$5") (pintype "bidirectional"))
    )
    (net (code "101") (name "unconnected-(U$1-PF1-OSC_OUT-PadP$6)") (class "Default")
      (node (ref "U$1") (pin "P$6") (pinfunction "PF1-OSC_OUT_P$6") (pintype "bidirectional"))
    )
  )
)
